# Power.net
KiCad netlist of a schematic drawn in Altium Designer
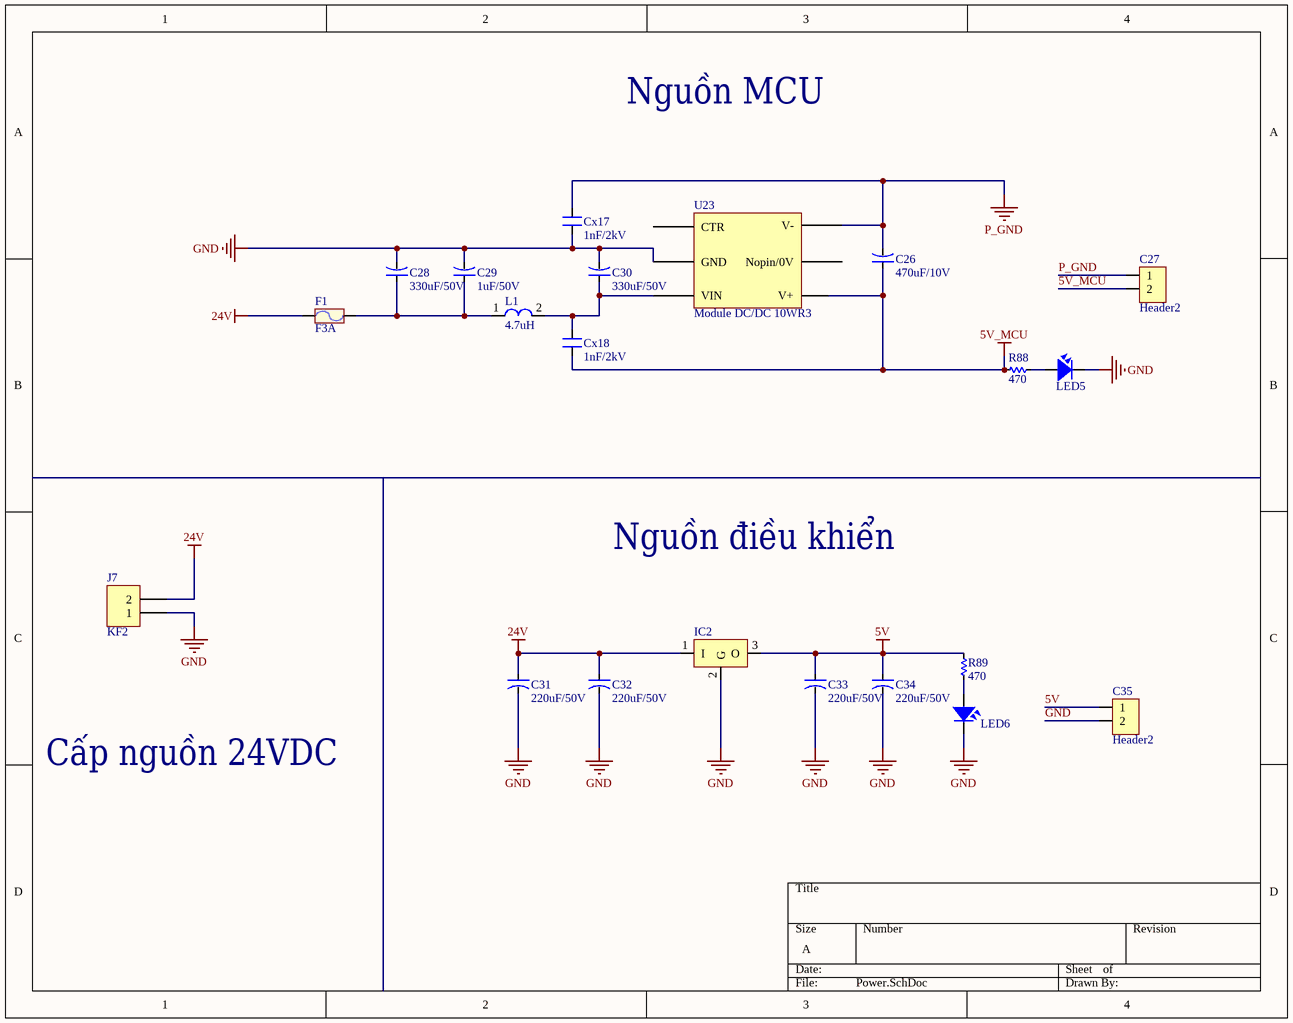
[diagram p0: Power.SchDoc]

(export (version "E")
  (design (tool "Eeschema 10.0.6"))
  (components
    (comp (ref "C26")
      (value "470uF/10V")
      (footprint "TANTALUM-7343")
      (libsource (lib "LIBRARY") (part "CN-TANTALUM-SMD"))
    )
    (comp (ref "C27")
      (value "Header2")
      (footprint "Header2")
      (description "Header IDC, 2 x 1 Pin Vertical 2.54mm Pitch (Non-Boxed, Male)")
      (fields
        (field (name "MANUFACTURER") "Würth Elektronik eiSos GmbH")
        (field (name "PARTNO") "613002143121")
        (field (name "CREATED BY") "Karrer Zheng")
      )
      (libsource (lib "LIBRARY") (part "Header2"))
    )
    (comp (ref "C28")
      (value "330uF/50V")
      (footprint "CAP-ALU-SMD-G")
      (description "Polarized Capacitor (Axial)")
      (fields (field (name "PUBLISHER") "Altium Limited"))
      (libsource (lib "LIBRARY") (part "CN-ALU-SMD"))
    )
    (comp (ref "C29")
      (value "1uF/50V")
      (footprint "CAP-ALU-SMD-4.5x5x1.4")
      (description "Polarized Capacitor (Axial)")
      (fields (field (name "PUBLISHER") "Altium Limited"))
      (libsource (lib "LIBRARY") (part "CN-ALU-SMD"))
    )
    (comp (ref "C30")
      (value "330uF/50V")
      (footprint "CAP-ALU-SMD-G")
      (description "Polarized Capacitor (Axial)")
      (fields (field (name "PUBLISHER") "Altium Limited"))
      (libsource (lib "LIBRARY") (part "CN-ALU-SMD"))
    )
    (comp (ref "C31")
      (value "220uF/50V")
      (footprint "CAP-ALU-SMD-6.3x7.7x2.2")
      (description "Polarized Capacitor (Axial)")
      (fields (field (name "PUBLISHER") "Altium Limited"))
      (libsource (lib "LIBRARY") (part "CN-ALU-SMD"))
    )
    (comp (ref "C32")
      (value "220uF/50V")
      (footprint "CAP-ALU-SMD-6.3x7.7x2.2")
      (description "Polarized Capacitor (Axial)")
      (fields (field (name "PUBLISHER") "Altium Limited"))
      (libsource (lib "LIBRARY") (part "CN-ALU-SMD"))
    )
    (comp (ref "C33")
      (value "220uF/50V")
      (footprint "CAP-ALU-SMD-6.3x7.7x2.2")
      (description "Polarized Capacitor (Axial)")
      (fields (field (name "PUBLISHER") "Altium Limited"))
      (libsource (lib "LIBRARY") (part "CN-ALU-SMD"))
    )
    (comp (ref "C34")
      (value "220uF/50V")
      (footprint "CAP-ALU-SMD-6.3x7.7x2.2")
      (description "Polarized Capacitor (Axial)")
      (fields (field (name "PUBLISHER") "Altium Limited"))
      (libsource (lib "LIBRARY") (part "CN-ALU-SMD"))
    )
    (comp (ref "C35")
      (value "Header2")
      (footprint "Header2")
      (description "Header IDC, 2 x 1 Pin Vertical 2.54mm Pitch (Non-Boxed, Male)")
      (fields
        (field (name "MANUFACTURER") "Würth Elektronik eiSos GmbH")
        (field (name "PARTNO") "613002143121")
        (field (name "CREATED BY") "Karrer Zheng")
      )
      (libsource (lib "LIBRARY") (part "Header2"))
    )
    (comp (ref "Cx17") (value "1nF/2kV") (footprint "CN2-B") (libsource (lib "LIBRARY") (part "CN")))
    (comp (ref "Cx18") (value "1nF/2kV") (footprint "CN2-B") (libsource (lib "LIBRARY") (part "CN")))
    (comp (ref "F1")
      (value "F3A")
      (footprint "FUSE_SMD 1812")
      (description "Fuse")
      (fields (field (name "DESIGNED BY") "VanDungEvn"))
      (libsource (lib "LIBRARY") (part "Fuse"))
    )
    (comp (ref "IC2")
      (value "LM78xx")
      (footprint "TO252-123")
      (description "Positive Voltage Regulator")
      (fields (field (name "PUBLISHER") "Altium Limited"))
      (libsource (lib "LIBRARY") (part "LM78xx"))
    )
    (comp (ref "J7")
      (value "KF2")
      (footprint "KF2-7.62")
      (fields
        (field (name "MANUFACTURER") "Würth Elektronik eiSos GmbH")
        (field (name "PARTNO") "691103110002")
        (field (name "CREATED BY") "Karrer Zheng")
      )
      (libsource (lib "LIBRARY") (part "KF2"))
    )
    (comp (ref "L1")
      (value "4.7uH")
      (footprint "L-SMD-M-12x10")
      (fields
        (field (name "PARTNO") "78477010")
        (field (name "MANUFACTURER") "Wurth Elektronik")
        (field (name "CREATED BY") "Baojun Chen")
      )
      (libsource (lib "LIBRARY") (part "L-SMD-1"))
    )
    (comp (ref "LED5") (value "LED") (footprint "LED-1206-Red") (libsource (lib "LIBRARY") (part "LED SMD")))
    (comp (ref "LED6") (value "LED") (footprint "LED-1206-Red") (libsource (lib "LIBRARY") (part "LED SMD")))
    (comp (ref "R88")
      (value "470")
      (footprint "RES-SMD-0805")
      (description "Resistor")
      (fields
        (field (name "MANUFACTURER") "Generic Components")
        (field (name "PUBLISHER") "Altium Hobart Technology Centre")
      )
      (libsource (lib "LIBRARY") (part "Res-SMD"))
    )
    (comp (ref "R89")
      (value "470")
      (footprint "RES-SMD-0805")
      (description "Resistor")
      (fields
        (field (name "MANUFACTURER") "Generic Components")
        (field (name "PUBLISHER") "Altium Hobart Technology Centre")
      )
      (libsource (lib "LIBRARY") (part "Res-SMD"))
    )
    (comp (ref "U23")
      (value "Module DC/DC 10WR3")
      (footprint "Module DC DC 10W/R3")
      (libsource (lib "LIBRARY") (part "Module DC/DC 10WR3"))
    )
  )
  (nets
    (net (code "1") (name "5V") (class "Default")
      (node (ref "C33") (pin "1") (pinfunction "1_1") (pintype "passive"))
      (node (ref "C34") (pin "1") (pinfunction "1_1") (pintype "passive"))
      (node (ref "C35") (pin "1") (pinfunction "1_1") (pintype "passive"))
      (node (ref "IC2") (pin "3") (pinfunction "O_3") (pintype "power_in"))
      (node (ref "R89") (pin "1") (pinfunction "1_1") (pintype "passive"))
    )
    (net (code "2") (name "5V_MCU") (class "Default")
      (node (ref "C26") (pin "1") (pinfunction "1_1") (pintype "passive"))
      (node (ref "C27") (pin "2") (pinfunction "2_2") (pintype "passive"))
      (node (ref "Cx18") (pin "1") (pinfunction "1_1") (pintype "passive"))
      (node (ref "R88") (pin "1") (pinfunction "1_1") (pintype "passive"))
      (node (ref "U23") (pin "V+") (pinfunction "V+_V+") (pintype "passive"))
    )
    (net (code "3") (name "24V") (class "Default")
      (node (ref "C31") (pin "1") (pinfunction "1_1") (pintype "passive"))
      (node (ref "C32") (pin "1") (pinfunction "1_1") (pintype "passive"))
      (node (ref "F1") (pin "1") (pinfunction "1_1") (pintype "passive"))
      (node (ref "IC2") (pin "1") (pinfunction "I_1") (pintype "power_in"))
      (node (ref "J7") (pin "2") (pinfunction "2_2") (pintype "passive"))
    )
    (net (code "4") (name "GND") (class "Default")
      (node (ref "C28") (pin "2") (pinfunction "2_2") (pintype "passive"))
      (node (ref "C29") (pin "2") (pinfunction "2_2") (pintype "passive"))
      (node (ref "C30") (pin "2") (pinfunction "2_2") (pintype "passive"))
      (node (ref "C31") (pin "2") (pinfunction "2_2") (pintype "passive"))
      (node (ref "C32") (pin "2") (pinfunction "2_2") (pintype "passive"))
      (node (ref "C33") (pin "2") (pinfunction "2_2") (pintype "passive"))
      (node (ref "C34") (pin "2") (pinfunction "2_2") (pintype "passive"))
      (node (ref "C35") (pin "2") (pinfunction "2_2") (pintype "passive"))
      (node (ref "Cx17") (pin "1") (pinfunction "1_1") (pintype "passive"))
      (node (ref "IC2") (pin "2") (pinfunction "G_2") (pintype "power_in"))
      (node (ref "J7") (pin "1") (pinfunction "1_1") (pintype "passive"))
      (node (ref "LED5") (pin "2") (pinfunction "2_2") (pintype "passive"))
      (node (ref "LED6") (pin "2") (pinfunction "2_2") (pintype "passive"))
      (node (ref "U23") (pin "GND") (pinfunction "GND_GND") (pintype "passive"))
    )
    (net (code "5") (name "Net-(C28-Pad1)") (class "Default")
      (node (ref "C28") (pin "1") (pinfunction "1_1") (pintype "passive"))
      (node (ref "C29") (pin "1") (pinfunction "1_1") (pintype "passive"))
      (node (ref "F1") (pin "2") (pinfunction "2_2") (pintype "passive"))
      (node (ref "L1") (pin "1") (pinfunction "1_1") (pintype "passive"))
    )
    (net (code "6") (name "Net-(C30-Pad1)") (class "Default")
      (node (ref "C30") (pin "1") (pinfunction "1_1") (pintype "passive"))
      (node (ref "Cx18") (pin "2") (pinfunction "2_2") (pintype "passive"))
      (node (ref "L1") (pin "2") (pinfunction "2_2") (pintype "passive"))
      (node (ref "U23") (pin "VIN") (pinfunction "VIN_VIN") (pintype "passive"))
    )
    (net (code "7") (name "Net-(LED5-Pad1)") (class "Default")
      (node (ref "LED5") (pin "1") (pinfunction "1_1") (pintype "passive"))
      (node (ref "R88") (pin "2") (pinfunction "2_2") (pintype "passive"))
    )
    (net (code "8") (name "Net-(LED6-Pad1)") (class "Default")
      (node (ref "LED6") (pin "1") (pinfunction "1_1") (pintype "passive"))
      (node (ref "R89") (pin "2") (pinfunction "2_2") (pintype "passive"))
    )
    (net (code "9") (name "P_GND") (class "Default")
      (node (ref "C26") (pin "2") (pinfunction "2_2") (pintype "passive"))
      (node (ref "C27") (pin "1") (pinfunction "1_1") (pintype "passive"))
      (node (ref "Cx17") (pin "2") (pinfunction "2_2") (pintype "passive"))
      (node (ref "U23") (pin "V-") (pinfunction "V-_V-") (pintype "passive"))
    )
    (net (code "10") (name "unconnected-(U23-PadCTR)") (class "Default")
      (node (ref "U23") (pin "CTR") (pinfunction "CTR_CTR") (pintype "passive"))
    )
    (net (code "11") (name "unconnected-(U23-PadNopin{slash}0V)") (class "Default")
      (node (ref "U23") (pin "Nopin/0V") (pinfunction "Nopin/0V_Nopin/0V") (pintype "passive"))
    )
  )
)
